# step-dir-single.net
KiCad netlist of a schematic drawn in Altium Designer
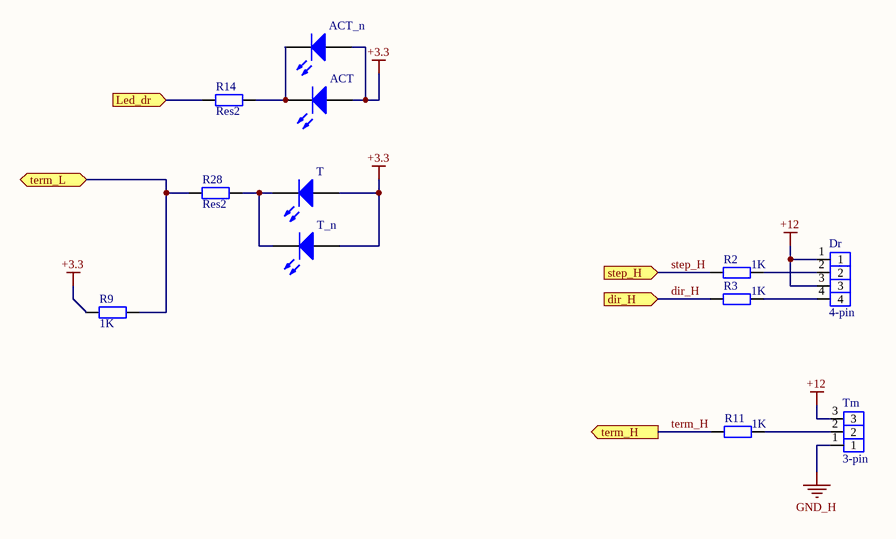
[diagram p0: step-dir-single.SchDoc]

(export (version "E")
  (design (tool "Eeschema 10.0.6"))
  (components
    (comp (ref "ACT")
      (value "led")
      (footprint "CD2012-0805")
      (description "chip led")
      (libsource (lib "Schlib1") (part "chip led"))
    )
    (comp (ref "ACT_n")
      (value "led")
      (footprint "led-pins")
      (description "chip led")
      (libsource (lib "Schlib1") (part "chip led"))
    )
    (comp (ref "Dr") (value "4-pin") (footprint "CWF-4R") (libsource (lib "Con sch") (part "4-pin")))
    (comp (ref "R2")
      (value "1K")
      (footprint "RESC2012M")
      (description "Resistor")
      (fields (field (name "PUBLISHER") "Altium Limited"))
      (libsource (lib "Miscellaneous Devices") (part "Res2"))
    )
    (comp (ref "R3")
      (value "1K")
      (footprint "RESC2012M")
      (description "Resistor")
      (fields (field (name "PUBLISHER") "Altium Limited"))
      (libsource (lib "Miscellaneous Devices") (part "Res2"))
    )
    (comp (ref "R9")
      (value "1K")
      (footprint "RESC2012M")
      (description "Resistor")
      (fields (field (name "PUBLISHER") "Altium Limited"))
      (libsource (lib "Miscellaneous Devices") (part "Res2"))
    )
    (comp (ref "R11")
      (value "1K")
      (footprint "RESC2012M")
      (description "Resistor")
      (fields (field (name "PUBLISHER") "Altium Limited"))
      (libsource (lib "Miscellaneous Devices") (part "Res2"))
    )
    (comp (ref "R14")
      (value "Res2")
      (footprint "RESC2012M")
      (description "Resistor")
      (fields (field (name "PUBLISHER") "Altium Limited"))
      (libsource (lib "Miscellaneous Devices") (part "Res2"))
    )
    (comp (ref "R28")
      (value "Res2")
      (footprint "RESC2012M")
      (description "Resistor")
      (fields (field (name "PUBLISHER") "Altium Limited"))
      (libsource (lib "Miscellaneous Devices") (part "Res2"))
    )
    (comp (ref "T")
      (value "led")
      (footprint "CD2012-0805")
      (description "chip led")
      (libsource (lib "Schlib1") (part "chip led"))
    )
    (comp (ref "Tm") (value "3-pin") (footprint "CWF-3R") (libsource (lib "Con sch") (part "3-pin")))
    (comp (ref "T_n")
      (value "led")
      (footprint "led-pins")
      (description "chip led")
      (libsource (lib "Schlib1") (part "chip led"))
    )
  )
  (nets
    (net (code "1") (name "+3.3") (class "Default")
      (node (ref "ACT") (pin "1") (pinfunction "A_1") (pintype "passive"))
      (node (ref "ACT_n") (pin "1") (pinfunction "A_1") (pintype "passive"))
      (node (ref "R9") (pin "1") (pinfunction "1_1") (pintype "passive"))
      (node (ref "T") (pin "1") (pinfunction "A_1") (pintype "passive"))
      (node (ref "T_n") (pin "1") (pinfunction "A_1") (pintype "passive"))
    )
    (net (code "2") (name "+12") (class "Default")
      (node (ref "Dr") (pin "1") (pinfunction "1_1") (pintype "passive"))
      (node (ref "Dr") (pin "3") (pinfunction "3_3") (pintype "passive"))
      (node (ref "Tm") (pin "3") (pinfunction "3_3") (pintype "passive"))
    )
    (net (code "3") (name "/Led_dr") (class "Default")
      (node (ref "R14") (pin "1") (pinfunction "1_1") (pintype "passive"))
    )
    (net (code "4") (name "/dir_H") (class "Default")
      (node (ref "R3") (pin "1") (pinfunction "1_1") (pintype "passive"))
    )
    (net (code "5") (name "/step_H") (class "Default")
      (node (ref "R2") (pin "1") (pinfunction "1_1") (pintype "passive"))
    )
    (net (code "6") (name "/term_H") (class "Default")
      (node (ref "R11") (pin "1") (pinfunction "1_1") (pintype "passive"))
    )
    (net (code "7") (name "/term_L") (class "Default")
      (node (ref "R28") (pin "1") (pinfunction "1_1") (pintype "passive"))
      (node (ref "R9") (pin "2") (pinfunction "2_2") (pintype "passive"))
    )
    (net (code "8") (name "GND_H") (class "Default")
      (node (ref "Tm") (pin "1") (pinfunction "1_1") (pintype "passive"))
    )
    (net (code "9") (name "Net-(ACT-K)") (class "Default")
      (node (ref "ACT") (pin "2") (pinfunction "K_2") (pintype "passive"))
      (node (ref "ACT_n") (pin "2") (pinfunction "K_2") (pintype "passive"))
      (node (ref "R14") (pin "2") (pinfunction "2_2") (pintype "passive"))
    )
    (net (code "10") (name "Net-(Dr-Pad2)") (class "Default")
      (node (ref "Dr") (pin "2") (pinfunction "2_2") (pintype "passive"))
      (node (ref "R2") (pin "2") (pinfunction "2_2") (pintype "passive"))
    )
    (net (code "11") (name "Net-(Dr-Pad4)") (class "Default")
      (node (ref "Dr") (pin "4") (pinfunction "4_4") (pintype "passive"))
      (node (ref "R3") (pin "2") (pinfunction "2_2") (pintype "passive"))
    )
    (net (code "12") (name "Net-(R11-Pad2)") (class "Default")
      (node (ref "R11") (pin "2") (pinfunction "2_2") (pintype "passive"))
      (node (ref "Tm") (pin "2") (pinfunction "2_2") (pintype "passive"))
    )
    (net (code "13") (name "Net-(T-K)") (class "Default")
      (node (ref "R28") (pin "2") (pinfunction "2_2") (pintype "passive"))
      (node (ref "T") (pin "2") (pinfunction "K_2") (pintype "passive"))
      (node (ref "T_n") (pin "2") (pinfunction "K_2") (pintype "passive"))
    )
  )
)
